# 3-ADC.net
KiCad netlist of a schematic drawn in Altium Designer
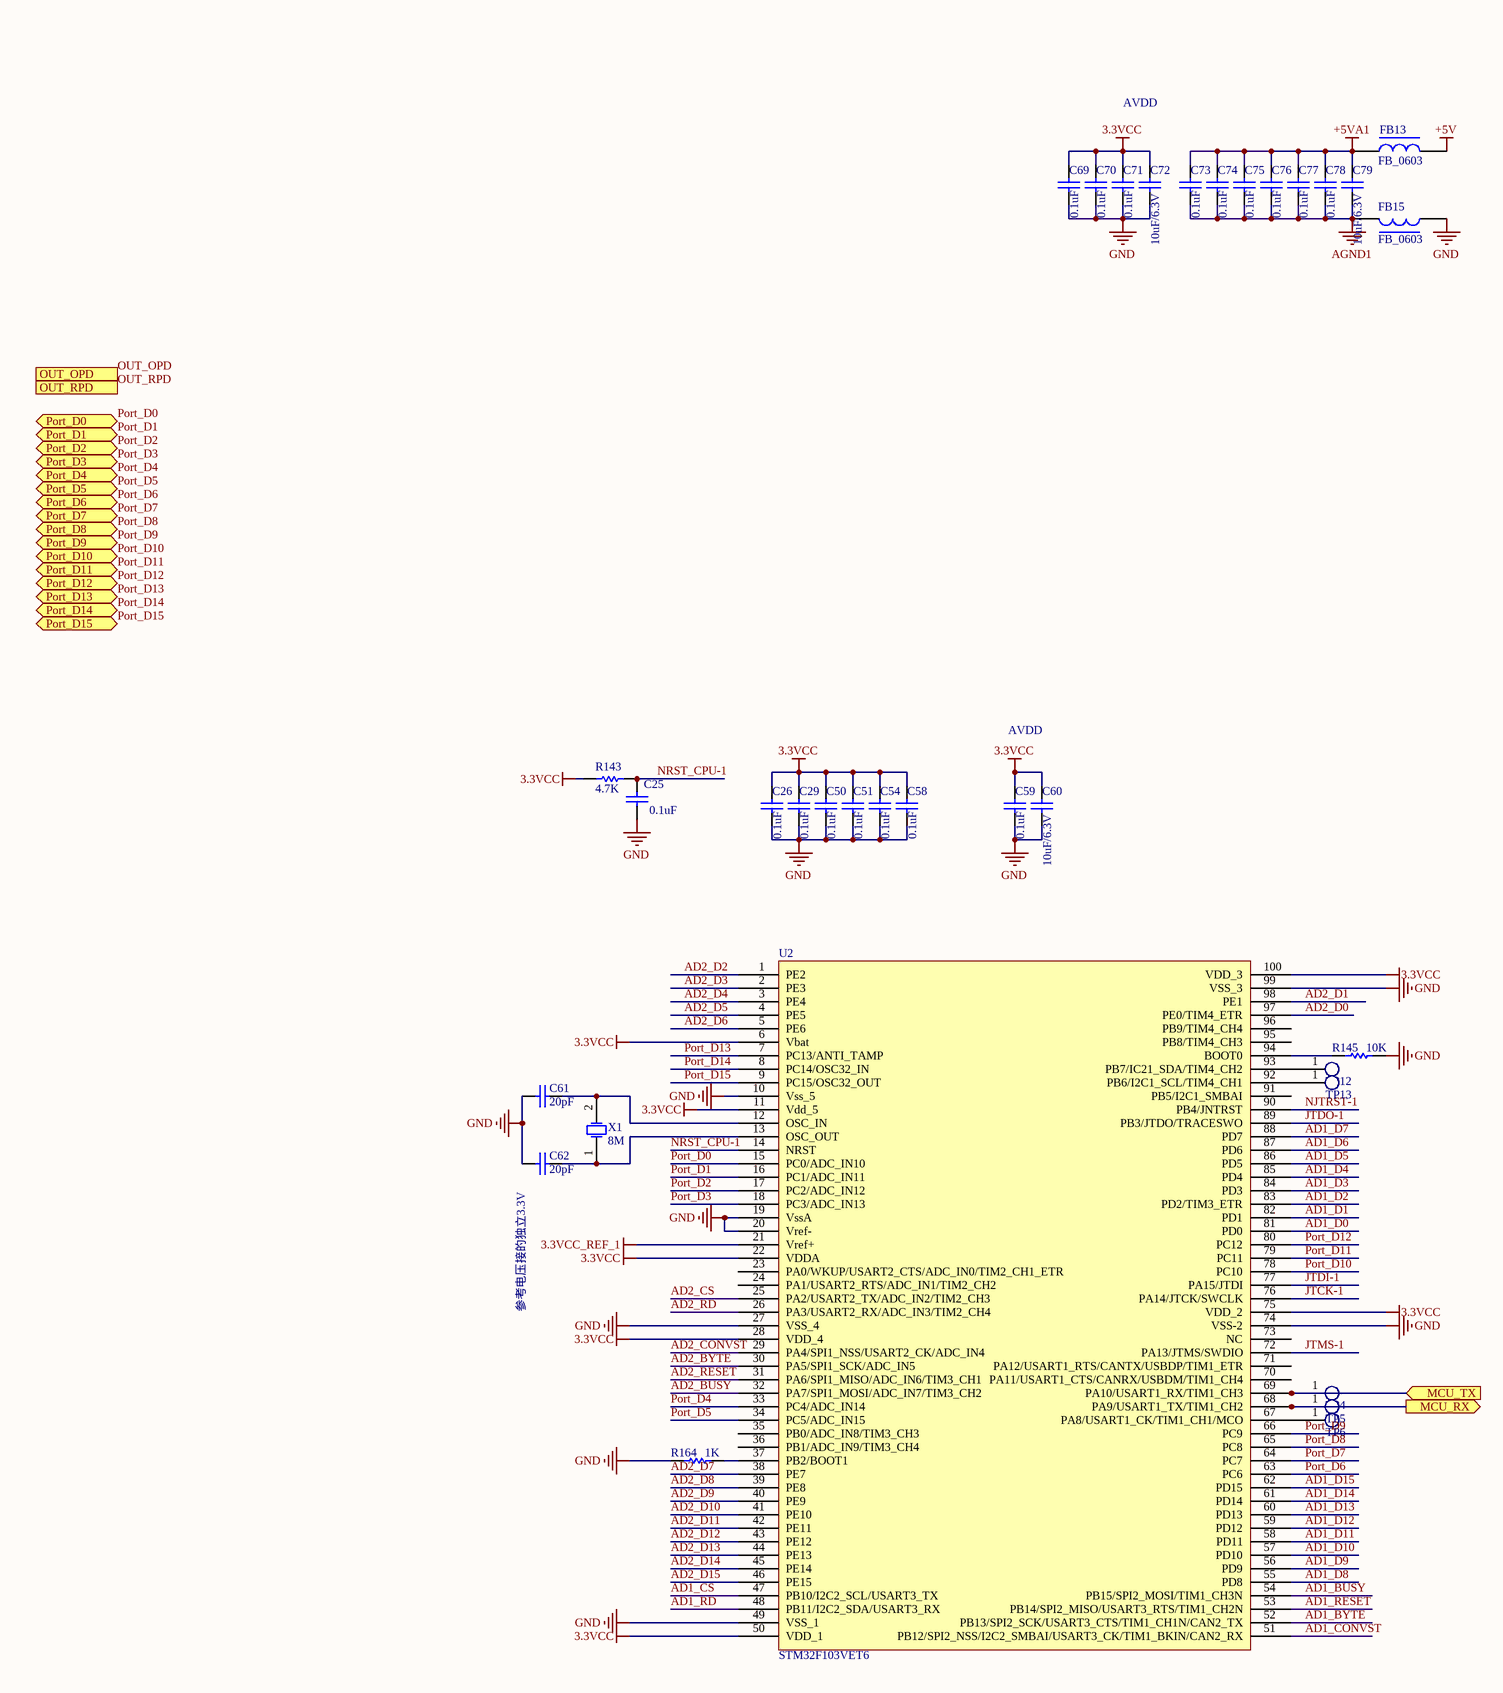
[diagram p0: 3-ADC.SchDoc, top left]
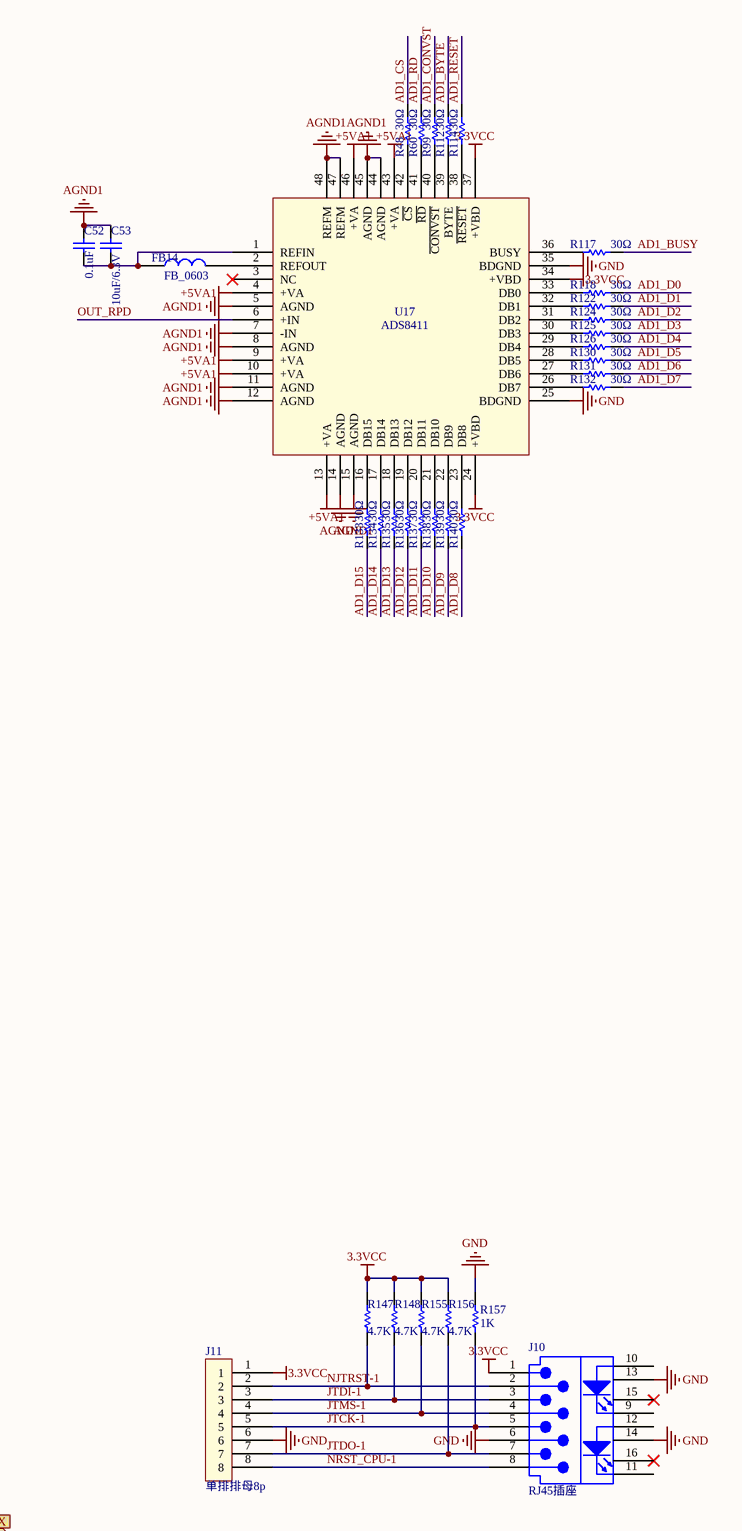
[diagram p1: 3-ADC.SchDoc, top right]
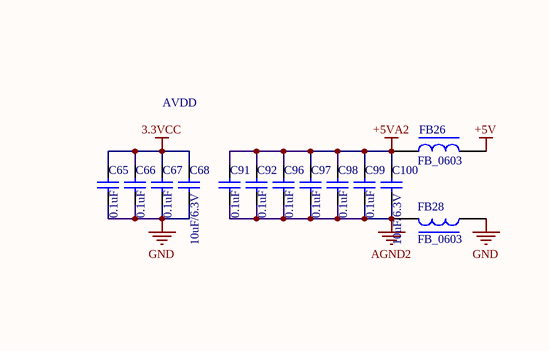
[diagram p2: 3-ADC.SchDoc, bottom left]
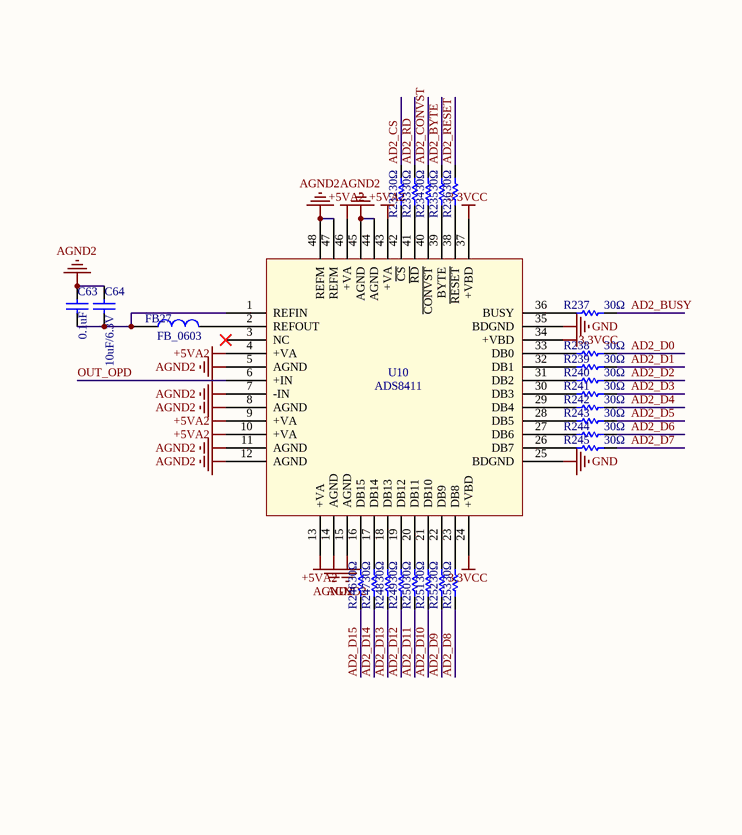
[diagram p3: 3-ADC.SchDoc, bottom right]

(export (version "E")
  (design (tool "Eeschema 10.0.6"))
  (components
    (comp (ref "C25")
      (value "0.1uF")
      (footprint "C0603")
      (description "贴片电容_GRM188R71H104KA01D_0.1uF±10%,50V,0603")
      (libsource (lib "20贴片电容0603") (part "0.1uF贴片电容"))
    )
    (comp (ref "C26")
      (value "0.1uF")
      (footprint "C0603")
      (description "贴片电容_GRM188R71H104KA01D_0.1uF±10%,50V,0603")
      (libsource (lib "20贴片电容0603") (part "0.1uF贴片电容"))
    )
    (comp (ref "C29")
      (value "0.1uF")
      (footprint "C0603")
      (description "贴片电容_GRM188R71H104KA01D_0.1uF±10%,50V,0603")
      (libsource (lib "20贴片电容0603") (part "0.1uF贴片电容"))
    )
    (comp (ref "C50")
      (value "0.1uF")
      (footprint "C0603")
      (description "贴片电容_GRM188R71H104KA01D_0.1uF±10%,50V,0603")
      (libsource (lib "20贴片电容0603") (part "0.1uF贴片电容"))
    )
    (comp (ref "C51")
      (value "0.1uF")
      (footprint "C0603")
      (description "贴片电容_GRM188R71H104KA01D_0.1uF±10%,50V,0603")
      (libsource (lib "20贴片电容0603") (part "0.1uF贴片电容"))
    )
    (comp (ref "C52")
      (value "0.1uF")
      (footprint "C0603")
      (description "贴片电容_GRM188R71H104KA01D_0.1uF±10%,50V,0603")
      (libsource (lib "20贴片电容0603") (part "0.1uF贴片电容"))
    )
    (comp (ref "C53")
      (value "10uF/6.3V")
      (footprint "C0603")
      (description "贴片电容_GRM188R60J106ME47D_10uF±20%,6.3V,0603")
      (libsource (lib "20贴片电容0603") (part "10uF贴片电容"))
    )
    (comp (ref "C54")
      (value "0.1uF")
      (footprint "C0603")
      (description "贴片电容_GRM188R71H104KA01D_0.1uF±10%,50V,0603")
      (libsource (lib "20贴片电容0603") (part "0.1uF贴片电容"))
    )
    (comp (ref "C58")
      (value "0.1uF")
      (footprint "C0603")
      (description "贴片电容_GRM188R71H104KA01D_0.1uF±10%,50V,0603")
      (libsource (lib "20贴片电容0603") (part "0.1uF贴片电容"))
    )
    (comp (ref "C59")
      (value "0.1uF")
      (footprint "C0603")
      (description "贴片电容_GRM188R71H104KA01D_0.1uF±10%,50V,0603")
      (libsource (lib "20贴片电容0603") (part "0.1uF贴片电容"))
    )
    (comp (ref "C60")
      (value "10uF/6.3V")
      (footprint "C0603")
      (description "贴片电容_GRM188R60J106ME47D_10uF±20%,6.3V,0603")
      (libsource (lib "20贴片电容0603") (part "10uF贴片电容"))
    )
    (comp (ref "C61")
      (value "20pF")
      (footprint "C0603")
      (description "贴片电容_GRM188C1H200JB01D_20pF±5%,50V,0603")
      (libsource (lib "20贴片电容0603") (part "20pF贴片电容"))
    )
    (comp (ref "C62")
      (value "20pF")
      (footprint "C0603")
      (description "贴片电容_GRM188C1H200JB01D_20pF±5%,50V,0603")
      (libsource (lib "20贴片电容0603") (part "20pF贴片电容"))
    )
    (comp (ref "C63")
      (value "0.1uF")
      (footprint "C0603")
      (description "贴片电容_GRM188R71H104KA01D_0.1uF±10%,50V,0603")
      (libsource (lib "20贴片电容0603") (part "0.1uF贴片电容"))
    )
    (comp (ref "C64")
      (value "10uF/6.3V")
      (footprint "C0603")
      (description "贴片电容_GRM188R60J106ME47D_10uF±20%,6.3V,0603")
      (libsource (lib "20贴片电容0603") (part "10uF贴片电容"))
    )
    (comp (ref "C65")
      (value "0.1uF")
      (footprint "C0603")
      (description "贴片电容_GRM188R71H104KA01D_0.1uF±10%,50V,0603")
      (libsource (lib "20贴片电容0603") (part "0.1uF贴片电容"))
    )
    (comp (ref "C66")
      (value "0.1uF")
      (footprint "C0603")
      (description "贴片电容_GRM188R71H104KA01D_0.1uF±10%,50V,0603")
      (libsource (lib "20贴片电容0603") (part "0.1uF贴片电容"))
    )
    (comp (ref "C67")
      (value "0.1uF")
      (footprint "C0603")
      (description "贴片电容_GRM188R71H104KA01D_0.1uF±10%,50V,0603")
      (libsource (lib "20贴片电容0603") (part "0.1uF贴片电容"))
    )
    (comp (ref "C68")
      (value "10uF/6.3V")
      (footprint "C0603")
      (description "贴片电容_GRM188R60J106ME47D_10uF±20%,6.3V,0603")
      (libsource (lib "20贴片电容0603") (part "10uF贴片电容"))
    )
    (comp (ref "C69")
      (value "0.1uF")
      (footprint "C0603")
      (description "贴片电容_GRM188R71H104KA01D_0.1uF±10%,50V,0603")
      (libsource (lib "20贴片电容0603") (part "0.1uF贴片电容"))
    )
    (comp (ref "C70")
      (value "0.1uF")
      (footprint "C0603")
      (description "贴片电容_GRM188R71H104KA01D_0.1uF±10%,50V,0603")
      (libsource (lib "20贴片电容0603") (part "0.1uF贴片电容"))
    )
    (comp (ref "C71")
      (value "0.1uF")
      (footprint "C0603")
      (description "贴片电容_GRM188R71H104KA01D_0.1uF±10%,50V,0603")
      (libsource (lib "20贴片电容0603") (part "0.1uF贴片电容"))
    )
    (comp (ref "C72")
      (value "10uF/6.3V")
      (footprint "C0603")
      (description "贴片电容_GRM188R60J106ME47D_10uF±20%,6.3V,0603")
      (libsource (lib "20贴片电容0603") (part "10uF贴片电容"))
    )
    (comp (ref "C73")
      (value "0.1uF")
      (footprint "C0603")
      (description "贴片电容_GRM188R71H104KA01D_0.1uF±10%,50V,0603")
      (libsource (lib "20贴片电容0603") (part "0.1uF贴片电容"))
    )
    (comp (ref "C74")
      (value "0.1uF")
      (footprint "C0603")
      (description "贴片电容_GRM188R71H104KA01D_0.1uF±10%,50V,0603")
      (libsource (lib "20贴片电容0603") (part "0.1uF贴片电容"))
    )
    (comp (ref "C75")
      (value "0.1uF")
      (footprint "C0603")
      (description "贴片电容_GRM188R71H104KA01D_0.1uF±10%,50V,0603")
      (libsource (lib "20贴片电容0603") (part "0.1uF贴片电容"))
    )
    (comp (ref "C76")
      (value "0.1uF")
      (footprint "C0603")
      (description "贴片电容_GRM188R71H104KA01D_0.1uF±10%,50V,0603")
      (libsource (lib "20贴片电容0603") (part "0.1uF贴片电容"))
    )
    (comp (ref "C77")
      (value "0.1uF")
      (footprint "C0603")
      (description "贴片电容_GRM188R71H104KA01D_0.1uF±10%,50V,0603")
      (libsource (lib "20贴片电容0603") (part "0.1uF贴片电容"))
    )
    (comp (ref "C78")
      (value "0.1uF")
      (footprint "C0603")
      (description "贴片电容_GRM188R71H104KA01D_0.1uF±10%,50V,0603")
      (libsource (lib "20贴片电容0603") (part "0.1uF贴片电容"))
    )
    (comp (ref "C79")
      (value "10uF/6.3V")
      (footprint "C0603")
      (description "贴片电容_GRM188R60J106ME47D_10uF±20%,6.3V,0603")
      (libsource (lib "20贴片电容0603") (part "10uF贴片电容"))
    )
    (comp (ref "C91")
      (value "0.1uF")
      (footprint "C0603")
      (description "贴片电容_GRM188R71H104KA01D_0.1uF±10%,50V,0603")
      (libsource (lib "20贴片电容0603") (part "0.1uF贴片电容"))
    )
    (comp (ref "C92")
      (value "0.1uF")
      (footprint "C0603")
      (description "贴片电容_GRM188R71H104KA01D_0.1uF±10%,50V,0603")
      (libsource (lib "20贴片电容0603") (part "0.1uF贴片电容"))
    )
    (comp (ref "C96")
      (value "0.1uF")
      (footprint "C0603")
      (description "贴片电容_GRM188R71H104KA01D_0.1uF±10%,50V,0603")
      (libsource (lib "20贴片电容0603") (part "0.1uF贴片电容"))
    )
    (comp (ref "C97")
      (value "0.1uF")
      (footprint "C0603")
      (description "贴片电容_GRM188R71H104KA01D_0.1uF±10%,50V,0603")
      (libsource (lib "20贴片电容0603") (part "0.1uF贴片电容"))
    )
    (comp (ref "C98")
      (value "0.1uF")
      (footprint "C0603")
      (description "贴片电容_GRM188R71H104KA01D_0.1uF±10%,50V,0603")
      (libsource (lib "20贴片电容0603") (part "0.1uF贴片电容"))
    )
    (comp (ref "C99")
      (value "0.1uF")
      (footprint "C0603")
      (description "贴片电容_GRM188R71H104KA01D_0.1uF±10%,50V,0603")
      (libsource (lib "20贴片电容0603") (part "0.1uF贴片电容"))
    )
    (comp (ref "C100")
      (value "10uF/6.3V")
      (footprint "C0603")
      (description "贴片电容_GRM188R60J106ME47D_10uF±20%,6.3V,0603")
      (libsource (lib "20贴片电容0603") (part "10uF贴片电容"))
    )
    (comp (ref "FB13")
      (value "FB_0603")
      (footprint "L0603")
      (description "贴片磁珠_100R,0603")
      (libsource (lib "32贴片磁珠0603") (part "0603贴片磁珠"))
    )
    (comp (ref "FB14")
      (value "FB_0603")
      (footprint "L0603")
      (description "贴片磁珠_100R,0603")
      (libsource (lib "32贴片磁珠0603") (part "0603贴片磁珠"))
    )
    (comp (ref "FB15")
      (value "FB_0603")
      (footprint "L0603")
      (description "贴片磁珠_100R,0603")
      (libsource (lib "32贴片磁珠0603") (part "0603贴片磁珠"))
    )
    (comp (ref "FB26")
      (value "FB_0603")
      (footprint "L0603")
      (description "贴片磁珠_100R,0603")
      (libsource (lib "32贴片磁珠0603") (part "0603贴片磁珠"))
    )
    (comp (ref "FB27")
      (value "FB_0603")
      (footprint "L0603")
      (description "贴片磁珠_100R,0603")
      (libsource (lib "32贴片磁珠0603") (part "0603贴片磁珠"))
    )
    (comp (ref "FB28")
      (value "FB_0603")
      (footprint "L0603")
      (description "贴片磁珠_100R,0603")
      (libsource (lib "32贴片磁珠0603") (part "0603贴片磁珠"))
    )
    (comp (ref "J10")
      (value "RJ45插座")
      (footprint "RJ45TH-1x1-2R54-LED")
      (description "RJ45插座_1*1,带左黄右绿灯,弯脚")
      (fields (field (name "MPN") "朱迅"))
      (libsource (lib "91连接器") (part "RJ45弯脚带灯"))
    )
    (comp (ref "J11")
      (value "单排排母8p")
      (footprint "SIP8TM-2R54")
      (description "连接器_单排排母座8p_直插,间距2.54mm")
      (fields (field (name "MPN") "WS"))
      (libsource (lib "90-连接器") (part "8p-2.54单排母座"))
    )
    (comp (ref "R48")
      (value "30Ω")
      (footprint "R0603")
      (description "贴片电阻_30Ω±5%,0603")
      (libsource (lib "10贴片电阻0603") (part "30Ω贴片电阻"))
    )
    (comp (ref "R60")
      (value "30Ω")
      (footprint "R0603")
      (description "贴片电阻_30Ω±5%,0603")
      (libsource (lib "10贴片电阻0603") (part "30Ω贴片电阻"))
    )
    (comp (ref "R99")
      (value "30Ω")
      (footprint "R0603")
      (description "贴片电阻_30Ω±5%,0603")
      (libsource (lib "10贴片电阻0603") (part "30Ω贴片电阻"))
    )
    (comp (ref "R112")
      (value "30Ω")
      (footprint "R0603")
      (description "贴片电阻_30Ω±5%,0603")
      (libsource (lib "10贴片电阻0603") (part "30Ω贴片电阻"))
    )
    (comp (ref "R114")
      (value "30Ω")
      (footprint "R0603")
      (description "贴片电阻_30Ω±5%,0603")
      (libsource (lib "10贴片电阻0603") (part "30Ω贴片电阻"))
    )
    (comp (ref "R117")
      (value "30Ω")
      (footprint "R0603")
      (description "贴片电阻_30Ω±5%,0603")
      (libsource (lib "10贴片电阻0603") (part "30Ω贴片电阻"))
    )
    (comp (ref "R118")
      (value "30Ω")
      (footprint "R0603")
      (description "贴片电阻_30Ω±5%,0603")
      (libsource (lib "10贴片电阻0603") (part "30Ω贴片电阻"))
    )
    (comp (ref "R122")
      (value "30Ω")
      (footprint "R0603")
      (description "贴片电阻_30Ω±5%,0603")
      (libsource (lib "10贴片电阻0603") (part "30Ω贴片电阻"))
    )
    (comp (ref "R124")
      (value "30Ω")
      (footprint "R0603")
      (description "贴片电阻_30Ω±5%,0603")
      (libsource (lib "10贴片电阻0603") (part "30Ω贴片电阻"))
    )
    (comp (ref "R125")
      (value "30Ω")
      (footprint "R0603")
      (description "贴片电阻_30Ω±5%,0603")
      (libsource (lib "10贴片电阻0603") (part "30Ω贴片电阻"))
    )
    (comp (ref "R126")
      (value "30Ω")
      (footprint "R0603")
      (description "贴片电阻_30Ω±5%,0603")
      (libsource (lib "10贴片电阻0603") (part "30Ω贴片电阻"))
    )
    (comp (ref "R130")
      (value "30Ω")
      (footprint "R0603")
      (description "贴片电阻_30Ω±5%,0603")
      (libsource (lib "10贴片电阻0603") (part "30Ω贴片电阻"))
    )
    (comp (ref "R131")
      (value "30Ω")
      (footprint "R0603")
      (description "贴片电阻_30Ω±5%,0603")
      (libsource (lib "10贴片电阻0603") (part "30Ω贴片电阻"))
    )
    (comp (ref "R132")
      (value "30Ω")
      (footprint "R0603")
      (description "贴片电阻_30Ω±5%,0603")
      (libsource (lib "10贴片电阻0603") (part "30Ω贴片电阻"))
    )
    (comp (ref "R133")
      (value "30Ω")
      (footprint "R0603")
      (description "贴片电阻_30Ω±5%,0603")
      (libsource (lib "10贴片电阻0603") (part "30Ω贴片电阻"))
    )
    (comp (ref "R134")
      (value "30Ω")
      (footprint "R0603")
      (description "贴片电阻_30Ω±5%,0603")
      (libsource (lib "10贴片电阻0603") (part "30Ω贴片电阻"))
    )
    (comp (ref "R135")
      (value "30Ω")
      (footprint "R0603")
      (description "贴片电阻_30Ω±5%,0603")
      (libsource (lib "10贴片电阻0603") (part "30Ω贴片电阻"))
    )
    (comp (ref "R136")
      (value "30Ω")
      (footprint "R0603")
      (description "贴片电阻_30Ω±5%,0603")
      (libsource (lib "10贴片电阻0603") (part "30Ω贴片电阻"))
    )
    (comp (ref "R137")
      (value "30Ω")
      (footprint "R0603")
      (description "贴片电阻_30Ω±5%,0603")
      (libsource (lib "10贴片电阻0603") (part "30Ω贴片电阻"))
    )
    (comp (ref "R138")
      (value "30Ω")
      (footprint "R0603")
      (description "贴片电阻_30Ω±5%,0603")
      (libsource (lib "10贴片电阻0603") (part "30Ω贴片电阻"))
    )
    (comp (ref "R139")
      (value "30Ω")
      (footprint "R0603")
      (description "贴片电阻_30Ω±5%,0603")
      (libsource (lib "10贴片电阻0603") (part "30Ω贴片电阻"))
    )
    (comp (ref "R140")
      (value "30Ω")
      (footprint "R0603")
      (description "贴片电阻_30Ω±5%,0603")
      (libsource (lib "10贴片电阻0603") (part "30Ω贴片电阻"))
    )
    (comp (ref "R143")
      (value "4.7K")
      (footprint "R0603")
      (description "贴片电阻_4.7K±5%,0603")
      (libsource (lib "10贴片电阻0603") (part "4.7K贴片电阻"))
    )
    (comp (ref "R145")
      (value "10K")
      (footprint "R0603")
      (description "贴片电阻_10K±5%,0603")
      (libsource (lib "10贴片电阻0603") (part "10K贴片电阻"))
    )
    (comp (ref "R147")
      (value "4.7K")
      (footprint "R0603")
      (description "贴片电阻_4.7K±5%,0603")
      (libsource (lib "10贴片电阻0603") (part "4.7K贴片电阻"))
    )
    (comp (ref "R148")
      (value "4.7K")
      (footprint "R0603")
      (description "贴片电阻_4.7K±5%,0603")
      (libsource (lib "10贴片电阻0603") (part "4.7K贴片电阻"))
    )
    (comp (ref "R155")
      (value "4.7K")
      (footprint "R0603")
      (description "贴片电阻_4.7K±5%,0603")
      (libsource (lib "10贴片电阻0603") (part "4.7K贴片电阻"))
    )
    (comp (ref "R156")
      (value "4.7K")
      (footprint "R0603")
      (description "贴片电阻_4.7K±5%,0603")
      (libsource (lib "10贴片电阻0603") (part "4.7K贴片电阻"))
    )
    (comp (ref "R157")
      (value "1K")
      (footprint "R0603")
      (description "贴片电阻_1K±5%,0603")
      (libsource (lib "10贴片电阻0603") (part "1K贴片电阻"))
    )
    (comp (ref "R164")
      (value "1K")
      (footprint "R0603")
      (description "贴片电阻_1K±5%,0603")
      (libsource (lib "10贴片电阻0603") (part "1K贴片电阻"))
    )
    (comp (ref "R232")
      (value "30Ω")
      (footprint "R0603")
      (description "贴片电阻_30Ω±5%,0603")
      (libsource (lib "10贴片电阻0603") (part "30Ω贴片电阻"))
    )
    (comp (ref "R233")
      (value "30Ω")
      (footprint "R0603")
      (description "贴片电阻_30Ω±5%,0603")
      (libsource (lib "10贴片电阻0603") (part "30Ω贴片电阻"))
    )
    (comp (ref "R234")
      (value "30Ω")
      (footprint "R0603")
      (description "贴片电阻_30Ω±5%,0603")
      (libsource (lib "10贴片电阻0603") (part "30Ω贴片电阻"))
    )
    (comp (ref "R235")
      (value "30Ω")
      (footprint "R0603")
      (description "贴片电阻_30Ω±5%,0603")
      (libsource (lib "10贴片电阻0603") (part "30Ω贴片电阻"))
    )
    (comp (ref "R236")
      (value "30Ω")
      (footprint "R0603")
      (description "贴片电阻_30Ω±5%,0603")
      (libsource (lib "10贴片电阻0603") (part "30Ω贴片电阻"))
    )
    (comp (ref "R237")
      (value "30Ω")
      (footprint "R0603")
      (description "贴片电阻_30Ω±5%,0603")
      (libsource (lib "10贴片电阻0603") (part "30Ω贴片电阻"))
    )
    (comp (ref "R238")
      (value "30Ω")
      (footprint "R0603")
      (description "贴片电阻_30Ω±5%,0603")
      (libsource (lib "10贴片电阻0603") (part "30Ω贴片电阻"))
    )
    (comp (ref "R239")
      (value "30Ω")
      (footprint "R0603")
      (description "贴片电阻_30Ω±5%,0603")
      (libsource (lib "10贴片电阻0603") (part "30Ω贴片电阻"))
    )
    (comp (ref "R240")
      (value "30Ω")
      (footprint "R0603")
      (description "贴片电阻_30Ω±5%,0603")
      (libsource (lib "10贴片电阻0603") (part "30Ω贴片电阻"))
    )
    (comp (ref "R241")
      (value "30Ω")
      (footprint "R0603")
      (description "贴片电阻_30Ω±5%,0603")
      (libsource (lib "10贴片电阻0603") (part "30Ω贴片电阻"))
    )
    (comp (ref "R242")
      (value "30Ω")
      (footprint "R0603")
      (description "贴片电阻_30Ω±5%,0603")
      (libsource (lib "10贴片电阻0603") (part "30Ω贴片电阻"))
    )
    (comp (ref "R243")
      (value "30Ω")
      (footprint "R0603")
      (description "贴片电阻_30Ω±5%,0603")
      (libsource (lib "10贴片电阻0603") (part "30Ω贴片电阻"))
    )
    (comp (ref "R244")
      (value "30Ω")
      (footprint "R0603")
      (description "贴片电阻_30Ω±5%,0603")
      (libsource (lib "10贴片电阻0603") (part "30Ω贴片电阻"))
    )
    (comp (ref "R245")
      (value "30Ω")
      (footprint "R0603")
      (description "贴片电阻_30Ω±5%,0603")
      (libsource (lib "10贴片电阻0603") (part "30Ω贴片电阻"))
    )
    (comp (ref "R246")
      (value "30Ω")
      (footprint "R0603")
      (description "贴片电阻_30Ω±5%,0603")
      (libsource (lib "10贴片电阻0603") (part "30Ω贴片电阻"))
    )
    (comp (ref "R247")
      (value "30Ω")
      (footprint "R0603")
      (description "贴片电阻_30Ω±5%,0603")
      (libsource (lib "10贴片电阻0603") (part "30Ω贴片电阻"))
    )
    (comp (ref "R248")
      (value "30Ω")
      (footprint "R0603")
      (description "贴片电阻_30Ω±5%,0603")
      (libsource (lib "10贴片电阻0603") (part "30Ω贴片电阻"))
    )
    (comp (ref "R249")
      (value "30Ω")
      (footprint "R0603")
      (description "贴片电阻_30Ω±5%,0603")
      (libsource (lib "10贴片电阻0603") (part "30Ω贴片电阻"))
    )
    (comp (ref "R250")
      (value "30Ω")
      (footprint "R0603")
      (description "贴片电阻_30Ω±5%,0603")
      (libsource (lib "10贴片电阻0603") (part "30Ω贴片电阻"))
    )
    (comp (ref "R251")
      (value "30Ω")
      (footprint "R0603")
      (description "贴片电阻_30Ω±5%,0603")
      (libsource (lib "10贴片电阻0603") (part "30Ω贴片电阻"))
    )
    (comp (ref "R252")
      (value "30Ω")
      (footprint "R0603")
      (description "贴片电阻_30Ω±5%,0603")
      (libsource (lib "10贴片电阻0603") (part "30Ω贴片电阻"))
    )
    (comp (ref "R253")
      (value "30Ω")
      (footprint "R0603")
      (description "贴片电阻_30Ω±5%,0603")
      (libsource (lib "10贴片电阻0603") (part "30Ω贴片电阻"))
    )
    (comp (ref "TP4")
      (value "TEST")
      (footprint "TP0R8")
      (description "表贴测试点0.8mm")
      (libsource (lib "92-其他（穿心电容，test等）") (part "TP0.8mm"))
    )
    (comp (ref "TP5")
      (value "TEST")
      (footprint "TP0R8")
      (description "表贴测试点0.8mm")
      (libsource (lib "92-其他（穿心电容，test等）") (part "TP0.8mm"))
    )
    (comp (ref "TP6")
      (value "TEST")
      (footprint "TP0R8")
      (description "表贴测试点0.8mm")
      (libsource (lib "92-其他（穿心电容，test等）") (part "TP0.8mm"))
    )
    (comp (ref "TP12")
      (value "TEST")
      (footprint "TP0R8")
      (description "表贴测试点0.8mm")
      (libsource (lib "92-其他（穿心电容，test等）") (part "TP0.8mm"))
    )
    (comp (ref "TP13")
      (value "TEST")
      (footprint "TP0R8")
      (description "表贴测试点0.8mm")
      (libsource (lib "92-其他（穿心电容，test等）") (part "TP0.8mm"))
    )
    (comp (ref "U2")
      (value "STM32F103VET6")
      (footprint "LQFP100_0R5_14x14")
      (description "MCU_STM32F103VET6_32 bit, LQFP100")
      (libsource (lib "71单片机") (part "STM32F103VET"))
    )
    (comp (ref "U10")
      (value "ADS8411")
      (footprint "TQFN48-0R5-7X7")
      (description "模数转换芯片_ADS8411_16-Bit,2MSPS,QFN48")
      (libsource (lib "88模数转换芯片") (part "ADS8411"))
    )
    (comp (ref "U17")
      (value "ADS8411")
      (footprint "TQFN48-0R5-7X7")
      (description "模数转换芯片_ADS8411_16-Bit,2MSPS,QFN48")
      (libsource (lib "88模数转换芯片") (part "ADS8411"))
    )
    (comp (ref "X1")
      (value "8M")
      (footprint "CRY2SM-6R0x3R5")
      (description "贴片无源晶体_8MHz,封装6035")
      (libsource (lib "60振荡器") (part "8M贴片无源晶体"))
    )
  )
  (nets
    (net (code "1") (name "+5V") (class "Default")
      (node (ref "FB13") (pin "2") (pinfunction "2_2") (pintype "passive"))
      (node (ref "FB26") (pin "2") (pinfunction "2_2") (pintype "passive"))
    )
    (net (code "2") (name "+5VA1") (class "Default")
      (node (ref "C73") (pin "2") (pinfunction "2_2") (pintype "passive"))
      (node (ref "C74") (pin "2") (pinfunction "2_2") (pintype "passive"))
      (node (ref "C75") (pin "2") (pinfunction "2_2") (pintype "passive"))
      (node (ref "C76") (pin "2") (pinfunction "2_2") (pintype "passive"))
      (node (ref "C77") (pin "2") (pinfunction "2_2") (pintype "passive"))
      (node (ref "C78") (pin "2") (pinfunction "2_2") (pintype "passive"))
      (node (ref "C79") (pin "2") (pinfunction "2_2") (pintype "passive"))
      (node (ref "FB13") (pin "1") (pinfunction "1_1") (pintype "passive"))
      (node (ref "U17") (pin "10") (pinfunction "+VA_10") (pintype "passive"))
      (node (ref "U17") (pin "13") (pinfunction "+VA_13") (pintype "passive"))
      (node (ref "U17") (pin "4") (pinfunction "+VA_4") (pintype "passive"))
      (node (ref "U17") (pin "43") (pinfunction "+VA_43") (pintype "passive"))
      (node (ref "U17") (pin "46") (pinfunction "+VA_46") (pintype "passive"))
      (node (ref "U17") (pin "9") (pinfunction "+VA_9") (pintype "passive"))
    )
    (net (code "3") (name "+5VA2") (class "Default")
      (node (ref "C100") (pin "2") (pinfunction "2_2") (pintype "passive"))
      (node (ref "C91") (pin "2") (pinfunction "2_2") (pintype "passive"))
      (node (ref "C92") (pin "2") (pinfunction "2_2") (pintype "passive"))
      (node (ref "C96") (pin "2") (pinfunction "2_2") (pintype "passive"))
      (node (ref "C97") (pin "2") (pinfunction "2_2") (pintype "passive"))
      (node (ref "C98") (pin "2") (pinfunction "2_2") (pintype "passive"))
      (node (ref "C99") (pin "2") (pinfunction "2_2") (pintype "passive"))
      (node (ref "FB26") (pin "1") (pinfunction "1_1") (pintype "passive"))
      (node (ref "U10") (pin "10") (pinfunction "+VA_10") (pintype "passive"))
      (node (ref "U10") (pin "13") (pinfunction "+VA_13") (pintype "passive"))
      (node (ref "U10") (pin "4") (pinfunction "+VA_4") (pintype "passive"))
      (node (ref "U10") (pin "43") (pinfunction "+VA_43") (pintype "passive"))
      (node (ref "U10") (pin "46") (pinfunction "+VA_46") (pintype "passive"))
      (node (ref "U10") (pin "9") (pinfunction "+VA_9") (pintype "passive"))
    )
    (net (code "4") (name "/AD1_BUSY") (class "Default")
      (node (ref "R117") (pin "2") (pinfunction "2_2") (pintype "passive"))
      (node (ref "U2") (pin "54") (pinfunction "PB15/SPI2_MOSI/TIM1_CH3N_54") (pintype "passive"))
    )
    (net (code "5") (name "/AD1_BYTE") (class "Default")
      (node (ref "R112") (pin "2") (pinfunction "2_2") (pintype "passive"))
      (node (ref "U2") (pin "52") (pinfunction "PB13/SPI2_SCK/USART3_CTS/TIM1_CH1N/CAN2_TX_52") (pintype "passive"))
    )
    (net (code "6") (name "/AD1_CONVST") (class "Default")
      (node (ref "R99") (pin "2") (pinfunction "2_2") (pintype "passive"))
      (node (ref "U2") (pin "51") (pinfunction "PB12/SPI2_NSS/I2C2_SMBAI/USART3_CK/TIM1_BKIN/CAN2_RX_51") (pintype "passive"))
    )
    (net (code "7") (name "/AD1_CS") (class "Default")
      (node (ref "R48") (pin "2") (pinfunction "2_2") (pintype "passive"))
      (node (ref "U2") (pin "47") (pinfunction "PB10/I2C2_SCL/USART3_TX_47") (pintype "passive"))
    )
    (net (code "8") (name "/AD1_D0") (class "Default")
      (node (ref "R118") (pin "2") (pinfunction "2_2") (pintype "passive"))
      (node (ref "U2") (pin "81") (pinfunction "PD0_81") (pintype "passive"))
    )
    (net (code "9") (name "/AD1_D1") (class "Default")
      (node (ref "R122") (pin "2") (pinfunction "2_2") (pintype "passive"))
      (node (ref "U2") (pin "82") (pinfunction "PD1_82") (pintype "passive"))
    )
    (net (code "10") (name "/AD1_D2") (class "Default")
      (node (ref "R124") (pin "2") (pinfunction "2_2") (pintype "passive"))
      (node (ref "U2") (pin "83") (pinfunction "PD2/TIM3_ETR_83") (pintype "passive"))
    )
    (net (code "11") (name "/AD1_D3") (class "Default")
      (node (ref "R125") (pin "2") (pinfunction "2_2") (pintype "passive"))
      (node (ref "U2") (pin "84") (pinfunction "PD3_84") (pintype "passive"))
    )
    (net (code "12") (name "/AD1_D4") (class "Default")
      (node (ref "R126") (pin "2") (pinfunction "2_2") (pintype "passive"))
      (node (ref "U2") (pin "85") (pinfunction "PD4_85") (pintype "passive"))
    )
    (net (code "13") (name "/AD1_D5") (class "Default")
      (node (ref "R130") (pin "2") (pinfunction "2_2") (pintype "passive"))
      (node (ref "U2") (pin "86") (pinfunction "PD5_86") (pintype "passive"))
    )
    (net (code "14") (name "/AD1_D6") (class "Default")
      (node (ref "R131") (pin "2") (pinfunction "2_2") (pintype "passive"))
      (node (ref "U2") (pin "87") (pinfunction "PD6_87") (pintype "passive"))
    )
    (net (code "15") (name "/AD1_D7") (class "Default")
      (node (ref "R132") (pin "2") (pinfunction "2_2") (pintype "passive"))
      (node (ref "U2") (pin "88") (pinfunction "PD7_88") (pintype "passive"))
    )
    (net (code "16") (name "/AD1_D8") (class "Default")
      (node (ref "R140") (pin "1") (pinfunction "1_1") (pintype "passive"))
      (node (ref "U2") (pin "55") (pinfunction "PD8_55") (pintype "passive"))
    )
    (net (code "17") (name "/AD1_D9") (class "Default")
      (node (ref "R139") (pin "1") (pinfunction "1_1") (pintype "passive"))
      (node (ref "U2") (pin "56") (pinfunction "PD9_56") (pintype "passive"))
    )
    (net (code "18") (name "/AD1_D10") (class "Default")
      (node (ref "R138") (pin "1") (pinfunction "1_1") (pintype "passive"))
      (node (ref "U2") (pin "57") (pinfunction "PD10_57") (pintype "passive"))
    )
    (net (code "19") (name "/AD1_D11") (class "Default")
      (node (ref "R137") (pin "1") (pinfunction "1_1") (pintype "passive"))
      (node (ref "U2") (pin "58") (pinfunction "PD11_58") (pintype "passive"))
    )
    (net (code "20") (name "/AD1_D12") (class "Default")
      (node (ref "R136") (pin "1") (pinfunction "1_1") (pintype "passive"))
      (node (ref "U2") (pin "59") (pinfunction "PD12_59") (pintype "passive"))
    )
    (net (code "21") (name "/AD1_D13") (class "Default")
      (node (ref "R135") (pin "1") (pinfunction "1_1") (pintype "passive"))
      (node (ref "U2") (pin "60") (pinfunction "PD13_60") (pintype "passive"))
    )
    (net (code "22") (name "/AD1_D14") (class "Default")
      (node (ref "R134") (pin "1") (pinfunction "1_1") (pintype "passive"))
      (node (ref "U2") (pin "61") (pinfunction "PD14_61") (pintype "passive"))
    )
    (net (code "23") (name "/AD1_D15") (class "Default")
      (node (ref "R133") (pin "1") (pinfunction "1_1") (pintype "passive"))
      (node (ref "U2") (pin "62") (pinfunction "PD15_62") (pintype "passive"))
    )
    (net (code "24") (name "/AD1_RD") (class "Default")
      (node (ref "R60") (pin "2") (pinfunction "2_2") (pintype "passive"))
      (node (ref "U2") (pin "48") (pinfunction "PB11/I2C2_SDA/USART3_RX_48") (pintype "passive"))
    )
    (net (code "25") (name "/AD1_RESET") (class "Default")
      (node (ref "R114") (pin "2") (pinfunction "2_2") (pintype "passive"))
      (node (ref "U2") (pin "53") (pinfunction "PB14/SPI2_MISO/USART3_RTS/TIM1_CH2N_53") (pintype "passive"))
    )
    (net (code "26") (name "/AD2_BUSY") (class "Default")
      (node (ref "R237") (pin "2") (pinfunction "2_2") (pintype "passive"))
      (node (ref "U2") (pin "32") (pinfunction "PA7/SPI1_MOSI/ADC_IN7/TIM3_CH2_32") (pintype "passive"))
    )
    (net (code "27") (name "/AD2_BYTE") (class "Default")
      (node (ref "R235") (pin "2") (pinfunction "2_2") (pintype "passive"))
      (node (ref "U2") (pin "30") (pinfunction "PA5/SPI1_SCK/ADC_IN5_30") (pintype "passive"))
    )
    (net (code "28") (name "/AD2_CONVST") (class "Default")
      (node (ref "R234") (pin "2") (pinfunction "2_2") (pintype "passive"))
      (node (ref "U2") (pin "29") (pinfunction "PA4/SPI1_NSS/USART2_CK/ADC_IN4_29") (pintype "passive"))
    )
    (net (code "29") (name "/AD2_CS") (class "Default")
      (node (ref "R232") (pin "2") (pinfunction "2_2") (pintype "passive"))
      (node (ref "U2") (pin "25") (pinfunction "PA2/USART2_TX/ADC_IN2/TIM2_CH3_25") (pintype "passive"))
    )
    (net (code "30") (name "/AD2_D0") (class "Default")
      (node (ref "R238") (pin "2") (pinfunction "2_2") (pintype "passive"))
      (node (ref "U2") (pin "97") (pinfunction "PE0/TIM4_ETR_97") (pintype "passive"))
    )
    (net (code "31") (name "/AD2_D1") (class "Default")
      (node (ref "R239") (pin "2") (pinfunction "2_2") (pintype "passive"))
      (node (ref "U2") (pin "98") (pinfunction "PE1_98") (pintype "passive"))
    )
    (net (code "32") (name "/AD2_D2") (class "Default")
      (node (ref "R240") (pin "2") (pinfunction "2_2") (pintype "passive"))
      (node (ref "U2") (pin "1") (pinfunction "PE2_1") (pintype "passive"))
    )
    (net (code "33") (name "/AD2_D3") (class "Default")
      (node (ref "R241") (pin "2") (pinfunction "2_2") (pintype "passive"))
      (node (ref "U2") (pin "2") (pinfunction "PE3_2") (pintype "passive"))
    )
    (net (code "34") (name "/AD2_D4") (class "Default")
      (node (ref "R242") (pin "2") (pinfunction "2_2") (pintype "passive"))
      (node (ref "U2") (pin "3") (pinfunction "PE4_3") (pintype "passive"))
    )
    (net (code "35") (name "/AD2_D5") (class "Default")
      (node (ref "R243") (pin "2") (pinfunction "2_2") (pintype "passive"))
      (node (ref "U2") (pin "4") (pinfunction "PE5_4") (pintype "passive"))
    )
    (net (code "36") (name "/AD2_D6") (class "Default")
      (node (ref "R244") (pin "2") (pinfunction "2_2") (pintype "passive"))
      (node (ref "U2") (pin "5") (pinfunction "PE6_5") (pintype "passive"))
    )
    (net (code "37") (name "/AD2_D7") (class "Default")
      (node (ref "R245") (pin "2") (pinfunction "2_2") (pintype "passive"))
      (node (ref "U2") (pin "38") (pinfunction "PE7_38") (pintype "passive"))
    )
    (net (code "38") (name "/AD2_D8") (class "Default")
      (node (ref "R253") (pin "1") (pinfunction "1_1") (pintype "passive"))
      (node (ref "U2") (pin "39") (pinfunction "PE8_39") (pintype "passive"))
    )
    (net (code "39") (name "/AD2_D9") (class "Default")
      (node (ref "R252") (pin "1") (pinfunction "1_1") (pintype "passive"))
      (node (ref "U2") (pin "40") (pinfunction "PE9_40") (pintype "passive"))
    )
    (net (code "40") (name "/AD2_D10") (class "Default")
      (node (ref "R251") (pin "1") (pinfunction "1_1") (pintype "passive"))
      (node (ref "U2") (pin "41") (pinfunction "PE10_41") (pintype "passive"))
    )
    (net (code "41") (name "/AD2_D11") (class "Default")
      (node (ref "R250") (pin "1") (pinfunction "1_1") (pintype "passive"))
      (node (ref "U2") (pin "42") (pinfunction "PE11_42") (pintype "passive"))
    )
    (net (code "42") (name "/AD2_D12") (class "Default")
      (node (ref "R249") (pin "1") (pinfunction "1_1") (pintype "passive"))
      (node (ref "U2") (pin "43") (pinfunction "PE12_43") (pintype "passive"))
    )
    (net (code "43") (name "/AD2_D13") (class "Default")
      (node (ref "R248") (pin "1") (pinfunction "1_1") (pintype "passive"))
      (node (ref "U2") (pin "44") (pinfunction "PE13_44") (pintype "passive"))
    )
    (net (code "44") (name "/AD2_D14") (class "Default")
      (node (ref "R247") (pin "1") (pinfunction "1_1") (pintype "passive"))
      (node (ref "U2") (pin "45") (pinfunction "PE14_45") (pintype "passive"))
    )
    (net (code "45") (name "/AD2_D15") (class "Default")
      (node (ref "R246") (pin "1") (pinfunction "1_1") (pintype "passive"))
      (node (ref "U2") (pin "46") (pinfunction "PE15_46") (pintype "passive"))
    )
    (net (code "46") (name "/AD2_RD") (class "Default")
      (node (ref "R233") (pin "2") (pinfunction "2_2") (pintype "passive"))
      (node (ref "U2") (pin "26") (pinfunction "PA3/USART2_RX/ADC_IN3/TIM2_CH4_26") (pintype "passive"))
    )
    (net (code "47") (name "/AD2_RESET") (class "Default")
      (node (ref "R236") (pin "2") (pinfunction "2_2") (pintype "passive"))
      (node (ref "U2") (pin "31") (pinfunction "PA6/SPI1_MISO/ADC_IN6/TIM3_CH1_31") (pintype "passive"))
    )
    (net (code "48") (name "/JTCK-1") (class "Default")
      (node (ref "J10") (pin "5") (pinfunction "NC_5") (pintype "passive"))
      (node (ref "J11") (pin "5") (pinfunction "5_5") (pintype "passive"))
      (node (ref "R157") (pin "2") (pinfunction "2_2") (pintype "passive"))
      (node (ref "U2") (pin "76") (pinfunction "PA14/JTCK/SWCLK_76") (pintype "passive"))
    )
    (net (code "49") (name "/JTDI-1") (class "Default")
      (node (ref "J10") (pin "3") (pinfunction "RX+_3") (pintype "passive"))
      (node (ref "J11") (pin "3") (pinfunction "3_3") (pintype "passive"))
      (node (ref "R148") (pin "1") (pinfunction "1_1") (pintype "passive"))
      (node (ref "U2") (pin "77") (pinfunction "PA15/JTDI_77") (pintype "passive"))
    )
    (net (code "50") (name "/JTDO-1") (class "Default")
      (node (ref "J10") (pin "7") (pinfunction "NC_7") (pintype "passive"))
      (node (ref "J11") (pin "7") (pinfunction "7_7") (pintype "passive"))
      (node (ref "R156") (pin "1") (pinfunction "1_1") (pintype "passive"))
      (node (ref "U2") (pin "89") (pinfunction "PB3/JTDO/TRACESWO_89") (pintype "passive"))
    )
    (net (code "51") (name "/JTMS-1") (class "Default")
      (node (ref "J10") (pin "4") (pinfunction "NC_4") (pintype "passive"))
      (node (ref "J11") (pin "4") (pinfunction "4_4") (pintype "passive"))
      (node (ref "R155") (pin "1") (pinfunction "1_1") (pintype "passive"))
      (node (ref "U2") (pin "72") (pinfunction "PA13/JTMS/SWDIO_72") (pintype "passive"))
    )
    (net (code "52") (name "/MCU_RX") (class "Default")
      (node (ref "TP5") (pin "1") (pinfunction "TP_1") (pintype "passive"))
      (node (ref "U2") (pin "68") (pinfunction "PA9/USART1_TX/TIM1_CH2_68") (pintype "passive"))
    )
    (net (code "53") (name "/MCU_TX") (class "Default")
      (node (ref "TP4") (pin "1") (pinfunction "TP_1") (pintype "passive"))
      (node (ref "U2") (pin "69") (pinfunction "PA10/USART1_RX/TIM1_CH3_69") (pintype "passive"))
    )
    (net (code "54") (name "/NJTRST-1") (class "Default")
      (node (ref "J10") (pin "2") (pinfunction "TX-_2") (pintype "passive"))
      (node (ref "J11") (pin "2") (pinfunction "2_2") (pintype "passive"))
      (node (ref "R147") (pin "1") (pinfunction "1_1") (pintype "passive"))
      (node (ref "U2") (pin "90") (pinfunction "PB4/JNTRST_90") (pintype "passive"))
    )
    (net (code "55") (name "/NRST_CPU-1") (class "Default")
      (node (ref "C25") (pin "2") (pinfunction "2_2") (pintype "passive"))
      (node (ref "J10") (pin "8") (pinfunction "NC_8") (pintype "passive"))
      (node (ref "J11") (pin "8") (pinfunction "8_8") (pintype "passive"))
      (node (ref "R143") (pin "1") (pinfunction "1_1") (pintype "passive"))
      (node (ref "U2") (pin "14") (pinfunction "NRST_14") (pintype "passive"))
    )
    (net (code "56") (name "/OUT_OPD") (class "Default")
      (node (ref "U10") (pin "6") (pinfunction "+IN_6") (pintype "passive"))
    )
    (net (code "57") (name "/OUT_RPD") (class "Default")
      (node (ref "U17") (pin "6") (pinfunction "+IN_6") (pintype "passive"))
    )
    (net (code "58") (name "/Port_D0") (class "Default")
      (node (ref "U2") (pin "15") (pinfunction "PC0/ADC_IN10_15") (pintype "passive"))
    )
    (net (code "59") (name "/Port_D1") (class "Default")
      (node (ref "U2") (pin "16") (pinfunction "PC1/ADC_IN11_16") (pintype "passive"))
    )
    (net (code "60") (name "/Port_D2") (class "Default")
      (node (ref "U2") (pin "17") (pinfunction "PC2/ADC_IN12_17") (pintype "passive"))
    )
    (net (code "61") (name "/Port_D3") (class "Default")
      (node (ref "U2") (pin "18") (pinfunction "PC3/ADC_IN13_18") (pintype "passive"))
    )
    (net (code "62") (name "/Port_D4") (class "Default")
      (node (ref "U2") (pin "33") (pinfunction "PC4/ADC_IN14_33") (pintype "passive"))
    )
    (net (code "63") (name "/Port_D5") (class "Default")
      (node (ref "U2") (pin "34") (pinfunction "PC5/ADC_IN15_34") (pintype "passive"))
    )
    (net (code "64") (name "/Port_D6") (class "Default")
      (node (ref "U2") (pin "63") (pinfunction "PC6_63") (pintype "passive"))
    )
    (net (code "65") (name "/Port_D7") (class "Default")
      (node (ref "U2") (pin "64") (pinfunction "PC7_64") (pintype "passive"))
    )
    (net (code "66") (name "/Port_D8") (class "Default")
      (node (ref "U2") (pin "65") (pinfunction "PC8_65") (pintype "passive"))
    )
    (net (code "67") (name "/Port_D9") (class "Default")
      (node (ref "U2") (pin "66") (pinfunction "PC9_66") (pintype "passive"))
    )
    (net (code "68") (name "/Port_D10") (class "Default")
      (node (ref "U2") (pin "78") (pinfunction "PC10_78") (pintype "passive"))
    )
    (net (code "69") (name "/Port_D11") (class "Default")
      (node (ref "U2") (pin "79") (pinfunction "PC11_79") (pintype "passive"))
    )
    (net (code "70") (name "/Port_D12") (class "Default")
      (node (ref "U2") (pin "80") (pinfunction "PC12_80") (pintype "passive"))
    )
    (net (code "71") (name "/Port_D13") (class "Default")
      (node (ref "U2") (pin "7") (pinfunction "PC13/ANTI_TAMP_7") (pintype "passive"))
    )
    (net (code "72") (name "/Port_D14") (class "Default")
      (node (ref "U2") (pin "8") (pinfunction "PC14/OSC32_IN_8") (pintype "passive"))
    )
    (net (code "73") (name "/Port_D15") (class "Default")
      (node (ref "U2") (pin "9") (pinfunction "PC15/OSC32_OUT_9") (pintype "passive"))
    )
    (net (code "74") (name "3.3VCC") (class "Default")
      (node (ref "C26") (pin "2") (pinfunction "2_2") (pintype "passive"))
      (node (ref "C29") (pin "2") (pinfunction "2_2") (pintype "passive"))
      (node (ref "C50") (pin "2") (pinfunction "2_2") (pintype "passive"))
      (node (ref "C51") (pin "2") (pinfunction "2_2") (pintype "passive"))
      (node (ref "C54") (pin "2") (pinfunction "2_2") (pintype "passive"))
      (node (ref "C58") (pin "2") (pinfunction "2_2") (pintype "passive"))
      (node (ref "C59") (pin "2") (pinfunction "2_2") (pintype "passive"))
      (node (ref "C60") (pin "2") (pinfunction "2_2") (pintype "passive"))
      (node (ref "C65") (pin "2") (pinfunction "2_2") (pintype "passive"))
      (node (ref "C66") (pin "2") (pinfunction "2_2") (pintype "passive"))
      (node (ref "C67") (pin "2") (pinfunction "2_2") (pintype "passive"))
      (node (ref "C68") (pin "2") (pinfunction "2_2") (pintype "passive"))
      (node (ref "C69") (pin "2") (pinfunction "2_2") (pintype "passive"))
      (node (ref "C70") (pin "2") (pinfunction "2_2") (pintype "passive"))
      (node (ref "C71") (pin "2") (pinfunction "2_2") (pintype "passive"))
      (node (ref "C72") (pin "2") (pinfunction "2_2") (pintype "passive"))
      (node (ref "J10") (pin "1") (pinfunction "TX+_1") (pintype "passive"))
      (node (ref "J11") (pin "1") (pinfunction "1_1") (pintype "passive"))
      (node (ref "R143") (pin "2") (pinfunction "2_2") (pintype "passive"))
      (node (ref "R147") (pin "2") (pinfunction "2_2") (pintype "passive"))
      (node (ref "R148") (pin "2") (pinfunction "2_2") (pintype "passive"))
      (node (ref "R155") (pin "2") (pinfunction "2_2") (pintype "passive"))
      (node (ref "R156") (pin "2") (pinfunction "2_2") (pintype "passive"))
      (node (ref "U10") (pin "24") (pinfunction "+VBD_24") (pintype "passive"))
      (node (ref "U10") (pin "34") (pinfunction "+VBD_34") (pintype "passive"))
      (node (ref "U10") (pin "37") (pinfunction "+VBD_37") (pintype "passive"))
      (node (ref "U17") (pin "24") (pinfunction "+VBD_24") (pintype "passive"))
      (node (ref "U17") (pin "34") (pinfunction "+VBD_34") (pintype "passive"))
      (node (ref "U17") (pin "37") (pinfunction "+VBD_37") (pintype "passive"))
      (node (ref "U2") (pin "100") (pinfunction "VDD_3_100") (pintype "passive"))
      (node (ref "U2") (pin "11") (pinfunction "Vdd_5_11") (pintype "passive"))
      (node (ref "U2") (pin "22") (pinfunction "VDDA_22") (pintype "passive"))
      (node (ref "U2") (pin "28") (pinfunction "VDD_4_28") (pintype "passive"))
      (node (ref "U2") (pin "50") (pinfunction "VDD_1_50") (pintype "passive"))
      (node (ref "U2") (pin "6") (pinfunction "Vbat_6") (pintype "passive"))
      (node (ref "U2") (pin "75") (pinfunction "VDD_2_75") (pintype "passive"))
    )
    (net (code "75") (name "3.3VCC_REF_1") (class "Default")
      (node (ref "U2") (pin "21") (pinfunction "Vref+_21") (pintype "passive"))
    )
    (net (code "76") (name "AGND1") (class "Default")
      (node (ref "C52") (pin "2") (pinfunction "2_2") (pintype "passive"))
      (node (ref "C53") (pin "2") (pinfunction "2_2") (pintype "passive"))
      (node (ref "C73") (pin "1") (pinfunction "1_1") (pintype "passive"))
      (node (ref "C74") (pin "1") (pinfunction "1_1") (pintype "passive"))
      (node (ref "C75") (pin "1") (pinfunction "1_1") (pintype "passive"))
      (node (ref "C76") (pin "1") (pinfunction "1_1") (pintype "passive"))
      (node (ref "C77") (pin "1") (pinfunction "1_1") (pintype "passive"))
      (node (ref "C78") (pin "1") (pinfunction "1_1") (pintype "passive"))
      (node (ref "C79") (pin "1") (pinfunction "1_1") (pintype "passive"))
      (node (ref "FB15") (pin "2") (pinfunction "2_2") (pintype "passive"))
      (node (ref "U17") (pin "11") (pinfunction "AGND_11") (pintype "passive"))
      (node (ref "U17") (pin "12") (pinfunction "AGND_12") (pintype "passive"))
      (node (ref "U17") (pin "14") (pinfunction "AGND_14") (pintype "passive"))
      (node (ref "U17") (pin "15") (pinfunction "AGND_15") (pintype "passive"))
      (node (ref "U17") (pin "44") (pinfunction "AGND_44") (pintype "passive"))
      (node (ref "U17") (pin "45") (pinfunction "AGND_45") (pintype "passive"))
      (node (ref "U17") (pin "47") (pinfunction "REFM_47") (pintype "passive"))
      (node (ref "U17") (pin "48") (pinfunction "REFM_48") (pintype "passive"))
      (node (ref "U17") (pin "5") (pinfunction "AGND_5") (pintype "passive"))
      (node (ref "U17") (pin "7") (pinfunction "-IN_7") (pintype "passive"))
      (node (ref "U17") (pin "8") (pinfunction "AGND_8") (pintype "passive"))
    )
    (net (code "77") (name "AGND2") (class "Default")
      (node (ref "C100") (pin "1") (pinfunction "1_1") (pintype "passive"))
      (node (ref "C63") (pin "2") (pinfunction "2_2") (pintype "passive"))
      (node (ref "C64") (pin "2") (pinfunction "2_2") (pintype "passive"))
      (node (ref "C91") (pin "1") (pinfunction "1_1") (pintype "passive"))
      (node (ref "C92") (pin "1") (pinfunction "1_1") (pintype "passive"))
      (node (ref "C96") (pin "1") (pinfunction "1_1") (pintype "passive"))
      (node (ref "C97") (pin "1") (pinfunction "1_1") (pintype "passive"))
      (node (ref "C98") (pin "1") (pinfunction "1_1") (pintype "passive"))
      (node (ref "C99") (pin "1") (pinfunction "1_1") (pintype "passive"))
      (node (ref "FB28") (pin "2") (pinfunction "2_2") (pintype "passive"))
      (node (ref "U10") (pin "11") (pinfunction "AGND_11") (pintype "passive"))
      (node (ref "U10") (pin "12") (pinfunction "AGND_12") (pintype "passive"))
      (node (ref "U10") (pin "14") (pinfunction "AGND_14") (pintype "passive"))
      (node (ref "U10") (pin "15") (pinfunction "AGND_15") (pintype "passive"))
      (node (ref "U10") (pin "44") (pinfunction "AGND_44") (pintype "passive"))
      (node (ref "U10") (pin "45") (pinfunction "AGND_45") (pintype "passive"))
      (node (ref "U10") (pin "47") (pinfunction "REFM_47") (pintype "passive"))
      (node (ref "U10") (pin "48") (pinfunction "REFM_48") (pintype "passive"))
      (node (ref "U10") (pin "5") (pinfunction "AGND_5") (pintype "passive"))
      (node (ref "U10") (pin "7") (pinfunction "-IN_7") (pintype "passive"))
      (node (ref "U10") (pin "8") (pinfunction "AGND_8") (pintype "passive"))
    )
    (net (code "78") (name "GND") (class "Default")
      (node (ref "C25") (pin "1") (pinfunction "1_1") (pintype "passive"))
      (node (ref "C26") (pin "1") (pinfunction "1_1") (pintype "passive"))
      (node (ref "C29") (pin "1") (pinfunction "1_1") (pintype "passive"))
      (node (ref "C50") (pin "1") (pinfunction "1_1") (pintype "passive"))
      (node (ref "C51") (pin "1") (pinfunction "1_1") (pintype "passive"))
      (node (ref "C54") (pin "1") (pinfunction "1_1") (pintype "passive"))
      (node (ref "C58") (pin "1") (pinfunction "1_1") (pintype "passive"))
      (node (ref "C59") (pin "1") (pinfunction "1_1") (pintype "passive"))
      (node (ref "C60") (pin "1") (pinfunction "1_1") (pintype "passive"))
      (node (ref "C61") (pin "2") (pinfunction "2_2") (pintype "passive"))
      (node (ref "C62") (pin "2") (pinfunction "2_2") (pintype "passive"))
      (node (ref "C65") (pin "1") (pinfunction "1_1") (pintype "passive"))
      (node (ref "C66") (pin "1") (pinfunction "1_1") (pintype "passive"))
      (node (ref "C67") (pin "1") (pinfunction "1_1") (pintype "passive"))
      (node (ref "C68") (pin "1") (pinfunction "1_1") (pintype "passive"))
      (node (ref "C69") (pin "1") (pinfunction "1_1") (pintype "passive"))
      (node (ref "C70") (pin "1") (pinfunction "1_1") (pintype "passive"))
      (node (ref "C71") (pin "1") (pinfunction "1_1") (pintype "passive"))
      (node (ref "C72") (pin "1") (pinfunction "1_1") (pintype "passive"))
      (node (ref "FB15") (pin "1") (pinfunction "1_1") (pintype "passive"))
      (node (ref "FB28") (pin "1") (pinfunction "1_1") (pintype "passive"))
      (node (ref "J10") (pin "13") (pinfunction "13_13") (pintype "passive"))
      (node (ref "J10") (pin "14") (pinfunction "14_14") (pintype "passive"))
      (node (ref "J10") (pin "6") (pinfunction "RX-_6") (pintype "passive"))
      (node (ref "J11") (pin "6") (pinfunction "6_6") (pintype "passive"))
      (node (ref "R145") (pin "1") (pinfunction "1_1") (pintype "passive"))
      (node (ref "R157") (pin "1") (pinfunction "1_1") (pintype "passive"))
      (node (ref "R164") (pin "1") (pinfunction "1_1") (pintype "passive"))
      (node (ref "U10") (pin "25") (pinfunction "BDGND_25") (pintype "passive"))
      (node (ref "U10") (pin "35") (pinfunction "BDGND_35") (pintype "passive"))
      (node (ref "U17") (pin "25") (pinfunction "BDGND_25") (pintype "passive"))
      (node (ref "U17") (pin "35") (pinfunction "BDGND_35") (pintype "passive"))
      (node (ref "U2") (pin "10") (pinfunction "Vss_5_10") (pintype "passive"))
      (node (ref "U2") (pin "19") (pinfunction "VssA_19") (pintype "passive"))
      (node (ref "U2") (pin "20") (pinfunction "Vref-_20") (pintype "passive"))
      (node (ref "U2") (pin "27") (pinfunction "VSS_4_27") (pintype "passive"))
      (node (ref "U2") (pin "49") (pinfunction "VSS_1_49") (pintype "passive"))
      (node (ref "U2") (pin "74") (pinfunction "VSS-2_74") (pintype "passive"))
      (node (ref "U2") (pin "99") (pinfunction "VSS_3_99") (pintype "passive"))
    )
    (net (code "79") (name "Net-(TP6-TP)") (class "Default")
      (node (ref "TP6") (pin "1") (pinfunction "TP_1") (pintype "passive"))
      (node (ref "U2") (pin "67") (pinfunction "PA8/USART1_CK/TIM1_CH1/MCO_67") (pintype "passive"))
    )
    (net (code "80") (name "Net-(TP12-TP)") (class "Default")
      (node (ref "TP12") (pin "1") (pinfunction "TP_1") (pintype "passive"))
      (node (ref "U2") (pin "93") (pinfunction "PB7/IC21_SDA/TIM4_CH2_93") (pintype "passive"))
    )
    (net (code "81") (name "Net-(TP13-TP)") (class "Default")
      (node (ref "TP13") (pin "1") (pinfunction "TP_1") (pintype "passive"))
      (node (ref "U2") (pin "92") (pinfunction "PB6/I2C1_SCL/TIM4_CH1_92") (pintype "passive"))
    )
    (net (code "82") (name "Net-(U2-BOOT0)") (class "Default")
      (node (ref "R145") (pin "2") (pinfunction "2_2") (pintype "passive"))
      (node (ref "U2") (pin "94") (pinfunction "BOOT0_94") (pintype "passive"))
    )
    (net (code "83") (name "Net-(U2-OSC_IN)") (class "Default")
      (node (ref "C61") (pin "1") (pinfunction "1_1") (pintype "passive"))
      (node (ref "U2") (pin "12") (pinfunction "OSC_IN_12") (pintype "passive"))
      (node (ref "X1") (pin "2") (pinfunction "OSC2_2") (pintype "passive"))
    )
    (net (code "84") (name "Net-(U2-OSC_OUT)") (class "Default")
      (node (ref "C62") (pin "1") (pinfunction "1_1") (pintype "passive"))
      (node (ref "U2") (pin "13") (pinfunction "OSC_OUT_13") (pintype "passive"))
      (node (ref "X1") (pin "1") (pinfunction "OSC1_1") (pintype "passive"))
    )
    (net (code "85") (name "Net-(U2-PB2{slash}BOOT1)") (class "Default")
      (node (ref "R164") (pin "2") (pinfunction "2_2") (pintype "passive"))
      (node (ref "U2") (pin "37") (pinfunction "PB2/BOOT1_37") (pintype "passive"))
    )
    (net (code "86") (name "Net-(U10-BUSY)") (class "Default")
      (node (ref "R237") (pin "1") (pinfunction "1_1") (pintype "passive"))
      (node (ref "U10") (pin "36") (pinfunction "BUSY_36") (pintype "passive"))
    )
    (net (code "87") (name "Net-(U10-BYTE)") (class "Default")
      (node (ref "R235") (pin "1") (pinfunction "1_1") (pintype "passive"))
      (node (ref "U10") (pin "39") (pinfunction "BYTE_39") (pintype "passive"))
    )
    (net (code "88") (name "Net-(U10-DB0)") (class "Default")
      (node (ref "R238") (pin "1") (pinfunction "1_1") (pintype "passive"))
      (node (ref "U10") (pin "33") (pinfunction "DB0_33") (pintype "passive"))
    )
    (net (code "89") (name "Net-(U10-DB1)") (class "Default")
      (node (ref "R239") (pin "1") (pinfunction "1_1") (pintype "passive"))
      (node (ref "U10") (pin "32") (pinfunction "DB1_32") (pintype "passive"))
    )
    (net (code "90") (name "Net-(U10-DB2)") (class "Default")
      (node (ref "R240") (pin "1") (pinfunction "1_1") (pintype "passive"))
      (node (ref "U10") (pin "31") (pinfunction "DB2_31") (pintype "passive"))
    )
    (net (code "91") (name "Net-(U10-DB3)") (class "Default")
      (node (ref "R241") (pin "1") (pinfunction "1_1") (pintype "passive"))
      (node (ref "U10") (pin "30") (pinfunction "DB3_30") (pintype "passive"))
    )
    (net (code "92") (name "Net-(U10-DB4)") (class "Default")
      (node (ref "R242") (pin "1") (pinfunction "1_1") (pintype "passive"))
      (node (ref "U10") (pin "29") (pinfunction "DB4_29") (pintype "passive"))
    )
    (net (code "93") (name "Net-(U10-DB5)") (class "Default")
      (node (ref "R243") (pin "1") (pinfunction "1_1") (pintype "passive"))
      (node (ref "U10") (pin "28") (pinfunction "DB5_28") (pintype "passive"))
    )
    (net (code "94") (name "Net-(U10-DB6)") (class "Default")
      (node (ref "R244") (pin "1") (pinfunction "1_1") (pintype "passive"))
      (node (ref "U10") (pin "27") (pinfunction "DB6_27") (pintype "passive"))
    )
    (net (code "95") (name "Net-(U10-DB7)") (class "Default")
      (node (ref "R245") (pin "1") (pinfunction "1_1") (pintype "passive"))
      (node (ref "U10") (pin "26") (pinfunction "DB7_26") (pintype "passive"))
    )
    (net (code "96") (name "Net-(U10-DB8)") (class "Default")
      (node (ref "R253") (pin "2") (pinfunction "2_2") (pintype "passive"))
      (node (ref "U10") (pin "23") (pinfunction "DB8_23") (pintype "passive"))
    )
    (net (code "97") (name "Net-(U10-DB9)") (class "Default")
      (node (ref "R252") (pin "2") (pinfunction "2_2") (pintype "passive"))
      (node (ref "U10") (pin "22") (pinfunction "DB9_22") (pintype "passive"))
    )
    (net (code "98") (name "Net-(U10-DB10)") (class "Default")
      (node (ref "R251") (pin "2") (pinfunction "2_2") (pintype "passive"))
      (node (ref "U10") (pin "21") (pinfunction "DB10_21") (pintype "passive"))
    )
    (net (code "99") (name "Net-(U10-DB11)") (class "Default")
      (node (ref "R250") (pin "2") (pinfunction "2_2") (pintype "passive"))
      (node (ref "U10") (pin "20") (pinfunction "DB11_20") (pintype "passive"))
    )
    (net (code "100") (name "Net-(U10-DB12)") (class "Default")
      (node (ref "R249") (pin "2") (pinfunction "2_2") (pintype "passive"))
      (node (ref "U10") (pin "19") (pinfunction "DB12_19") (pintype "passive"))
    )
    (net (code "101") (name "Net-(U10-DB13)") (class "Default")
      (node (ref "R248") (pin "2") (pinfunction "2_2") (pintype "passive"))
      (node (ref "U10") (pin "18") (pinfunction "DB13_18") (pintype "passive"))
    )
    (net (code "102") (name "Net-(U10-DB14)") (class "Default")
      (node (ref "R247") (pin "2") (pinfunction "2_2") (pintype "passive"))
      (node (ref "U10") (pin "17") (pinfunction "DB14_17") (pintype "passive"))
    )
    (net (code "103") (name "Net-(U10-DB15)") (class "Default")
      (node (ref "R246") (pin "2") (pinfunction "2_2") (pintype "passive"))
      (node (ref "U10") (pin "16") (pinfunction "DB15_16") (pintype "passive"))
    )
    (net (code "104") (name "Net-(U10-REFIN)") (class "Default")
      (node (ref "C63") (pin "1") (pinfunction "1_1") (pintype "passive"))
      (node (ref "C64") (pin "1") (pinfunction "1_1") (pintype "passive"))
      (node (ref "FB27") (pin "1") (pinfunction "1_1") (pintype "passive"))
      (node (ref "U10") (pin "1") (pinfunction "REFIN_1") (pintype "passive"))
    )
    (net (code "105") (name "Net-(U10-REFOUT)") (class "Default")
      (node (ref "FB27") (pin "2") (pinfunction "2_2") (pintype "passive"))
      (node (ref "U10") (pin "2") (pinfunction "REFOUT_2") (pintype "passive"))
    )
    (net (code "106") (name "Net-(U10-~{CONVST})") (class "Default")
      (node (ref "R234") (pin "1") (pinfunction "1_1") (pintype "passive"))
      (node (ref "U10") (pin "40") (pinfunction "~{CONVST}_40") (pintype "passive"))
    )
    (net (code "107") (name "Net-(U10-~{CS})") (class "Default")
      (node (ref "R232") (pin "1") (pinfunction "1_1") (pintype "passive"))
      (node (ref "U10") (pin "42") (pinfunction "~{CS}_42") (pintype "passive"))
    )
    (net (code "108") (name "Net-(U10-~{RD})") (class "Default")
      (node (ref "R233") (pin "1") (pinfunction "1_1") (pintype "passive"))
      (node (ref "U10") (pin "41") (pinfunction "~{RD}_41") (pintype "passive"))
    )
    (net (code "109") (name "Net-(U10-~{RESET})") (class "Default")
      (node (ref "R236") (pin "1") (pinfunction "1_1") (pintype "passive"))
      (node (ref "U10") (pin "38") (pinfunction "~{RESET}_38") (pintype "passive"))
    )
    (net (code "110") (name "Net-(U17-BUSY)") (class "Default")
      (node (ref "R117") (pin "1") (pinfunction "1_1") (pintype "passive"))
      (node (ref "U17") (pin "36") (pinfunction "BUSY_36") (pintype "passive"))
    )
    (net (code "111") (name "Net-(U17-BYTE)") (class "Default")
      (node (ref "R112") (pin "1") (pinfunction "1_1") (pintype "passive"))
      (node (ref "U17") (pin "39") (pinfunction "BYTE_39") (pintype "passive"))
    )
    (net (code "112") (name "Net-(U17-DB0)") (class "Default")
      (node (ref "R118") (pin "1") (pinfunction "1_1") (pintype "passive"))
      (node (ref "U17") (pin "33") (pinfunction "DB0_33") (pintype "passive"))
    )
    (net (code "113") (name "Net-(U17-DB1)") (class "Default")
      (node (ref "R122") (pin "1") (pinfunction "1_1") (pintype "passive"))
      (node (ref "U17") (pin "32") (pinfunction "DB1_32") (pintype "passive"))
    )
    (net (code "114") (name "Net-(U17-DB2)") (class "Default")
      (node (ref "R124") (pin "1") (pinfunction "1_1") (pintype "passive"))
      (node (ref "U17") (pin "31") (pinfunction "DB2_31") (pintype "passive"))
    )
    (net (code "115") (name "Net-(U17-DB3)") (class "Default")
      (node (ref "R125") (pin "1") (pinfunction "1_1") (pintype "passive"))
      (node (ref "U17") (pin "30") (pinfunction "DB3_30") (pintype "passive"))
    )
    (net (code "116") (name "Net-(U17-DB4)") (class "Default")
      (node (ref "R126") (pin "1") (pinfunction "1_1") (pintype "passive"))
      (node (ref "U17") (pin "29") (pinfunction "DB4_29") (pintype "passive"))
    )
    (net (code "117") (name "Net-(U17-DB5)") (class "Default")
      (node (ref "R130") (pin "1") (pinfunction "1_1") (pintype "passive"))
      (node (ref "U17") (pin "28") (pinfunction "DB5_28") (pintype "passive"))
    )
    (net (code "118") (name "Net-(U17-DB6)") (class "Default")
      (node (ref "R131") (pin "1") (pinfunction "1_1") (pintype "passive"))
      (node (ref "U17") (pin "27") (pinfunction "DB6_27") (pintype "passive"))
    )
    (net (code "119") (name "Net-(U17-DB7)") (class "Default")
      (node (ref "R132") (pin "1") (pinfunction "1_1") (pintype "passive"))
      (node (ref "U17") (pin "26") (pinfunction "DB7_26") (pintype "passive"))
    )
    (net (code "120") (name "Net-(U17-DB8)") (class "Default")
      (node (ref "R140") (pin "2") (pinfunction "2_2") (pintype "passive"))
      (node (ref "U17") (pin "23") (pinfunction "DB8_23") (pintype "passive"))
    )
    (net (code "121") (name "Net-(U17-DB9)") (class "Default")
      (node (ref "R139") (pin "2") (pinfunction "2_2") (pintype "passive"))
      (node (ref "U17") (pin "22") (pinfunction "DB9_22") (pintype "passive"))
    )
    (net (code "122") (name "Net-(U17-DB10)") (class "Default")
      (node (ref "R138") (pin "2") (pinfunction "2_2") (pintype "passive"))
      (node (ref "U17") (pin "21") (pinfunction "DB10_21") (pintype "passive"))
    )
    (net (code "123") (name "Net-(U17-DB11)") (class "Default")
      (node (ref "R137") (pin "2") (pinfunction "2_2") (pintype "passive"))
      (node (ref "U17") (pin "20") (pinfunction "DB11_20") (pintype "passive"))
    )
    (net (code "124") (name "Net-(U17-DB12)") (class "Default")
      (node (ref "R136") (pin "2") (pinfunction "2_2") (pintype "passive"))
      (node (ref "U17") (pin "19") (pinfunction "DB12_19") (pintype "passive"))
    )
    (net (code "125") (name "Net-(U17-DB13)") (class "Default")
      (node (ref "R135") (pin "2") (pinfunction "2_2") (pintype "passive"))
      (node (ref "U17") (pin "18") (pinfunction "DB13_18") (pintype "passive"))
    )
    (net (code "126") (name "Net-(U17-DB14)") (class "Default")
      (node (ref "R134") (pin "2") (pinfunction "2_2") (pintype "passive"))
      (node (ref "U17") (pin "17") (pinfunction "DB14_17") (pintype "passive"))
    )
    (net (code "127") (name "Net-(U17-DB15)") (class "Default")
      (node (ref "R133") (pin "2") (pinfunction "2_2") (pintype "passive"))
      (node (ref "U17") (pin "16") (pinfunction "DB15_16") (pintype "passive"))
    )
    (net (code "128") (name "Net-(U17-REFIN)") (class "Default")
      (node (ref "C52") (pin "1") (pinfunction "1_1") (pintype "passive"))
      (node (ref "C53") (pin "1") (pinfunction "1_1") (pintype "passive"))
      (node (ref "FB14") (pin "1") (pinfunction "1_1") (pintype "passive"))
      (node (ref "U17") (pin "1") (pinfunction "REFIN_1") (pintype "passive"))
    )
    (net (code "129") (name "Net-(U17-REFOUT)") (class "Default")
      (node (ref "FB14") (pin "2") (pinfunction "2_2") (pintype "passive"))
      (node (ref "U17") (pin "2") (pinfunction "REFOUT_2") (pintype "passive"))
    )
    (net (code "130") (name "Net-(U17-~{CONVST})") (class "Default")
      (node (ref "R99") (pin "1") (pinfunction "1_1") (pintype "passive"))
      (node (ref "U17") (pin "40") (pinfunction "~{CONVST}_40") (pintype "passive"))
    )
    (net (code "131") (name "Net-(U17-~{CS})") (class "Default")
      (node (ref "R48") (pin "1") (pinfunction "1_1") (pintype "passive"))
      (node (ref "U17") (pin "42") (pinfunction "~{CS}_42") (pintype "passive"))
    )
    (net (code "132") (name "Net-(U17-~{RD})") (class "Default")
      (node (ref "R60") (pin "1") (pinfunction "1_1") (pintype "passive"))
      (node (ref "U17") (pin "41") (pinfunction "~{RD}_41") (pintype "passive"))
    )
    (net (code "133") (name "Net-(U17-~{RESET})") (class "Default")
      (node (ref "R114") (pin "1") (pinfunction "1_1") (pintype "passive"))
      (node (ref "U17") (pin "38") (pinfunction "~{RESET}_38") (pintype "passive"))
    )
    (net (code "134") (name "unconnected-(J10-A1-Pad10)") (class "Default")
      (node (ref "J10") (pin "10") (pinfunction "A1_10") (pintype "passive"))
    )
    (net (code "135") (name "unconnected-(J10-A2-Pad12)") (class "Default")
      (node (ref "J10") (pin "12") (pinfunction "A2_12") (pintype "passive"))
    )
    (net (code "136") (name "unconnected-(J10-K1-Pad9)") (class "Default")
      (node (ref "J10") (pin "9") (pinfunction "K1_9") (pintype "passive"))
    )
    (net (code "137") (name "unconnected-(J10-K2-Pad11)") (class "Default")
      (node (ref "J10") (pin "11") (pinfunction "K2_11") (pintype "passive"))
    )
    (net (code "138") (name "unconnected-(J10-Pad15)") (class "Default")
      (node (ref "J10") (pin "15") (pinfunction "15_15") (pintype "passive+no_connect"))
    )
    (net (code "139") (name "unconnected-(J10-Pad16)") (class "Default")
      (node (ref "J10") (pin "16") (pinfunction "16_16") (pintype "passive+no_connect"))
    )
    (net (code "140") (name "unconnected-(U2-NC-Pad73)") (class "Default")
      (node (ref "U2") (pin "73") (pinfunction "NC_73") (pintype "passive"))
    )
    (net (code "141") (name "unconnected-(U2-PA0{slash}WKUP{slash}USART2_CTS{slash}ADC_IN0{slash}TIM2_CH1_ETR-Pad23)") (class "Default")
      (node (ref "U2") (pin "23") (pinfunction "PA0/WKUP/USART2_CTS/ADC_IN0/TIM2_CH1_ETR_23") (pintype "passive"))
    )
    (net (code "142") (name "unconnected-(U2-PA1{slash}USART2_RTS{slash}ADC_IN1{slash}TIM2_CH2-Pad24)") (class "Default")
      (node (ref "U2") (pin "24") (pinfunction "PA1/USART2_RTS/ADC_IN1/TIM2_CH2_24") (pintype "passive"))
    )
    (net (code "143") (name "unconnected-(U2-PA11{slash}USART1_CTS{slash}CANRX{slash}USBDM{slash}TIM1_CH4-Pad70)") (class "Default")
      (node (ref "U2") (pin "70") (pinfunction "PA11/USART1_CTS/CANRX/USBDM/TIM1_CH4_70") (pintype "passive"))
    )
    (net (code "144") (name "unconnected-(U2-PA12{slash}USART1_RTS{slash}CANTX{slash}USBDP{slash}TIM1_ETR-Pad71)") (class "Default")
      (node (ref "U2") (pin "71") (pinfunction "PA12/USART1_RTS/CANTX/USBDP/TIM1_ETR_71") (pintype "passive"))
    )
    (net (code "145") (name "unconnected-(U2-PB0{slash}ADC_IN8{slash}TIM3_CH3-Pad35)") (class "Default")
      (node (ref "U2") (pin "35") (pinfunction "PB0/ADC_IN8/TIM3_CH3_35") (pintype "passive"))
    )
    (net (code "146") (name "unconnected-(U2-PB1{slash}ADC_IN9{slash}TIM3_CH4-Pad36)") (class "Default")
      (node (ref "U2") (pin "36") (pinfunction "PB1/ADC_IN9/TIM3_CH4_36") (pintype "passive"))
    )
    (net (code "147") (name "unconnected-(U2-PB5{slash}I2C1_SMBAI-Pad91)") (class "Default")
      (node (ref "U2") (pin "91") (pinfunction "PB5/I2C1_SMBAI_91") (pintype "passive"))
    )
    (net (code "148") (name "unconnected-(U2-PB8{slash}TIM4_CH3-Pad95)") (class "Default")
      (node (ref "U2") (pin "95") (pinfunction "PB8/TIM4_CH3_95") (pintype "passive"))
    )
    (net (code "149") (name "unconnected-(U2-PB9{slash}TIM4_CH4-Pad96)") (class "Default")
      (node (ref "U2") (pin "96") (pinfunction "PB9/TIM4_CH4_96") (pintype "passive"))
    )
    (net (code "150") (name "unconnected-(U10-NC-Pad3)") (class "Default")
      (node (ref "U10") (pin "3") (pinfunction "NC_3") (pintype "passive+no_connect"))
    )
    (net (code "151") (name "unconnected-(U17-NC-Pad3)") (class "Default")
      (node (ref "U17") (pin "3") (pinfunction "NC_3") (pintype "passive+no_connect"))
    )
  )
)
